# ProDocument_Schematic1_2023-08-22.net
KiCad netlist of a schematic drawn in EasyEDA Pro
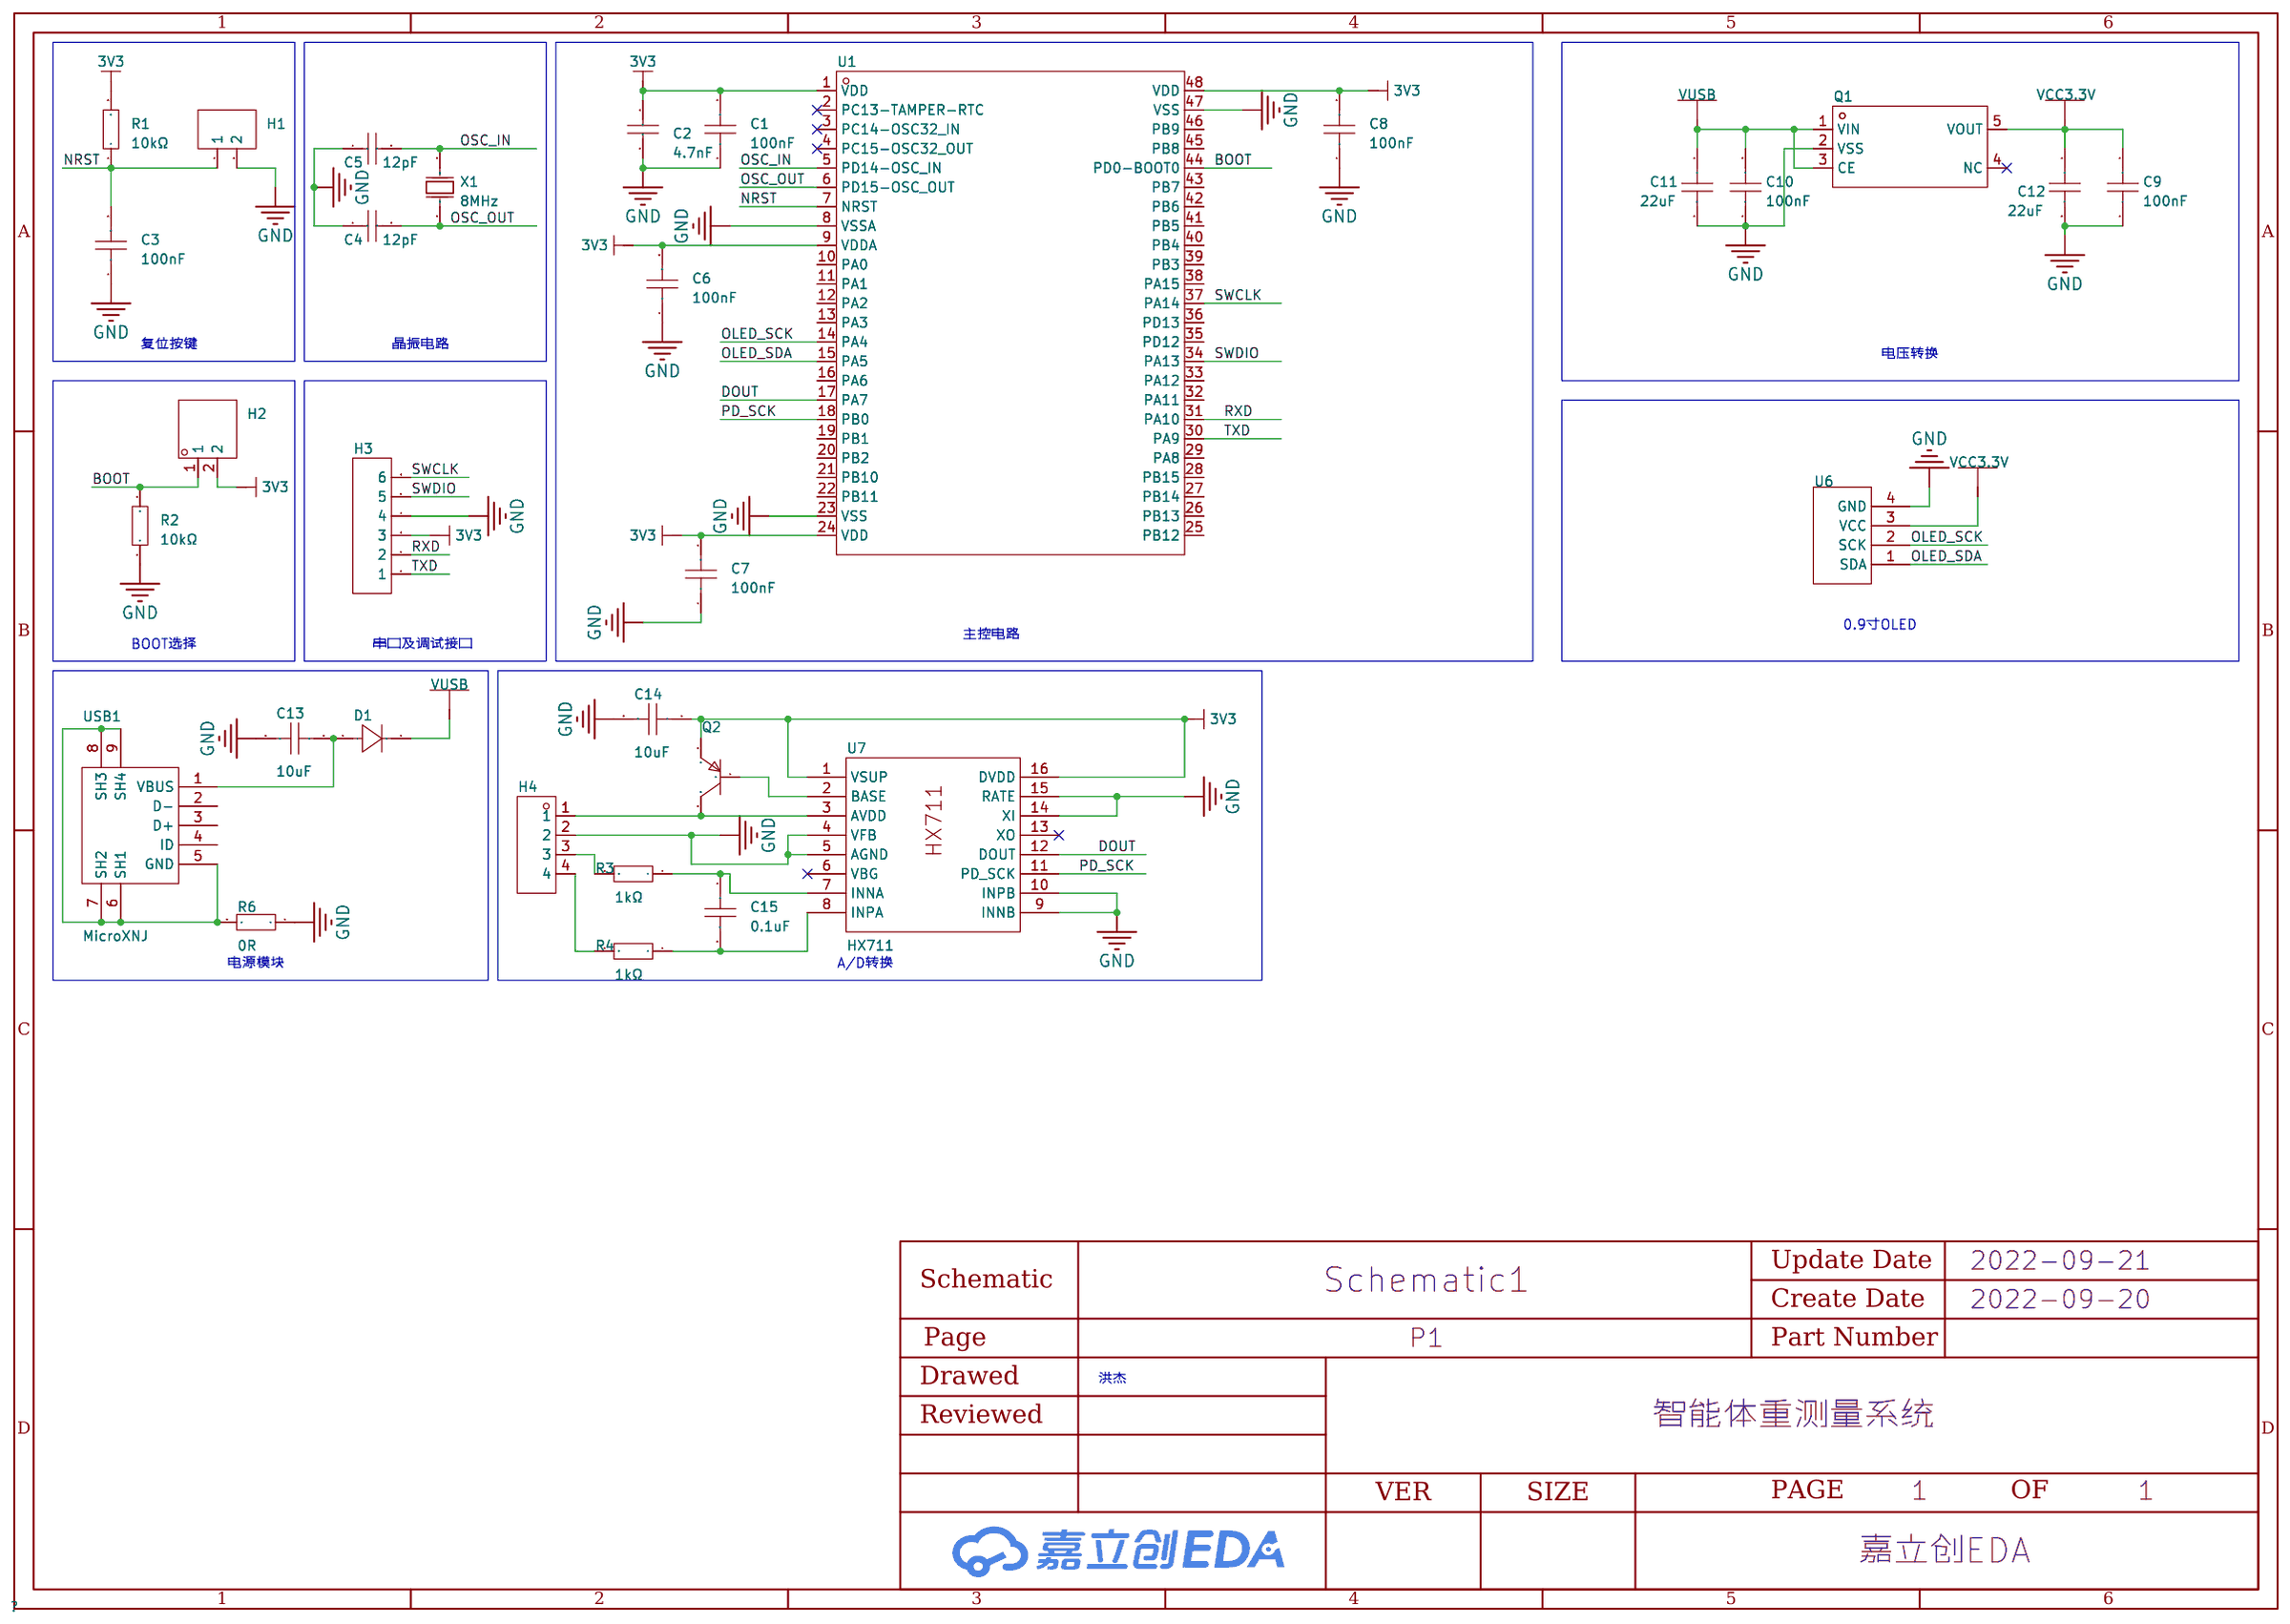
[diagram p0: schematic sheet]

(export (version "E")
  (design (tool "Eeschema 10.0.6"))
  (components
    (comp (ref "C1")
      (value "100nF")
      (footprint "easyedapro:C0603")
      (description "容值:100nF;精度:±10%;额定电压:50V;材质(温度系数):X7R;")
      (fields
        (field (name "Manufacturer Part") "CC0603KRX7R9BB104")
        (field (name "Manufacturer") "YAGEO(国巨)")
      )
      (libsource (lib "easyedapro") (part "CC0603KRX7R9BB104"))
    )
    (comp (ref "C2")
      (value "4.7nF")
      (footprint "easyedapro:C1206")
      (description "容值:4.7nF;精度:±10%;额定电压:1kV;材质(温度系数):X7R;")
      (fields (field (name "Manufacturer Part") "1206B472K102NT") (field (name "Manufacturer") "FH(风华)"))
      (libsource (lib "easyedapro") (part "1206B472K102NT"))
    )
    (comp (ref "C3")
      (value "100nF")
      (footprint "easyedapro:C0603")
      (description "容值:100nF;精度:±10%;额定电压:50V;材质(温度系数):X7R;")
      (fields
        (field (name "Manufacturer Part") "CC0603KRX7R9BB104")
        (field (name "Manufacturer") "YAGEO(国巨)")
      )
      (libsource (lib "easyedapro") (part "CC0603KRX7R9BB104"))
    )
    (comp (ref "C4")
      (value "12pF")
      (footprint "easyedapro:C0603")
      (description "温度系数:C0G;容值:12pF;精度:±5%;额定电压:50V;")
      (fields
        (field (name "Manufacturer Part") "CL10C120JB8NNNC")
        (field (name "Manufacturer") "SAMSUNG(三星)")
      )
      (libsource (lib "easyedapro") (part "CL10C120JB8NNNC"))
    )
    (comp (ref "C5")
      (value "12pF")
      (footprint "easyedapro:C0603")
      (description "温度系数:C0G;容值:12pF;精度:±5%;额定电压:50V;")
      (fields
        (field (name "Manufacturer Part") "CL10C120JB8NNNC")
        (field (name "Manufacturer") "SAMSUNG(三星)")
      )
      (libsource (lib "easyedapro") (part "CL10C120JB8NNNC"))
    )
    (comp (ref "C6")
      (value "100nF")
      (footprint "easyedapro:C0603")
      (description "容值:100nF;精度:±10%;额定电压:50V;材质(温度系数):X7R;")
      (fields
        (field (name "Manufacturer Part") "CC0603KRX7R9BB104")
        (field (name "Manufacturer") "YAGEO(国巨)")
      )
      (libsource (lib "easyedapro") (part "CC0603KRX7R9BB104"))
    )
    (comp (ref "C7")
      (value "100nF")
      (footprint "easyedapro:C0603")
      (description "容值:100nF;精度:±10%;额定电压:50V;材质(温度系数):X7R;")
      (fields
        (field (name "Manufacturer Part") "CC0603KRX7R9BB104")
        (field (name "Manufacturer") "YAGEO(国巨)")
      )
      (libsource (lib "easyedapro") (part "CC0603KRX7R9BB104"))
    )
    (comp (ref "C8")
      (value "100nF")
      (footprint "easyedapro:C0603")
      (description "容值:100nF;精度:±10%;额定电压:50V;材质(温度系数):X7R;")
      (fields
        (field (name "Manufacturer Part") "CC0603KRX7R9BB104")
        (field (name "Manufacturer") "YAGEO(国巨)")
      )
      (libsource (lib "easyedapro") (part "CC0603KRX7R9BB104"))
    )
    (comp (ref "C9")
      (value "100nF")
      (footprint "easyedapro:C0603")
      (description "容值:100nF;精度:±10%;额定电压:100V;温度系数:X7R;")
      (fields
        (field (name "Manufacturer Part") "HMK107B7104KA-T")
        (field (name "Manufacturer") "TAIYO YUDEN(太诱)")
      )
      (libsource (lib "easyedapro") (part "HMK107B7104KA-T"))
    )
    (comp (ref "C10")
      (value "100nF")
      (footprint "easyedapro:C0603")
      (description "容值:100nF;精度:±10%;额定电压:100V;温度系数:X7R;")
      (fields
        (field (name "Manufacturer Part") "HMK107B7104KA-T")
        (field (name "Manufacturer") "TAIYO YUDEN(太诱)")
      )
      (libsource (lib "easyedapro") (part "HMK107B7104KA-T"))
    )
    (comp (ref "C11")
      (value "22uF")
      (footprint "easyedapro:C0603")
      (description "容值:22uF;精度:±20%;额定电压:6.3V;温度系数:X5R;")
      (fields
        (field (name "Manufacturer Part") "GRM186R60J226ME15D")
        (field (name "Manufacturer") "muRata(村田)")
      )
      (libsource (lib "easyedapro") (part "GRM186R60J226ME15D"))
    )
    (comp (ref "C12")
      (value "22uF")
      (footprint "easyedapro:C0603")
      (description "容值:22uF;精度:±20%;额定电压:6.3V;温度系数:X5R;")
      (fields
        (field (name "Manufacturer Part") "GRM186R60J226ME15D")
        (field (name "Manufacturer") "muRata(村田)")
      )
      (libsource (lib "easyedapro") (part "GRM186R60J226ME15D"))
    )
    (comp (ref "C13")
      (value "10uF")
      (footprint "easyedapro:C0603")
      (description "容值:100nF;精度:±10%;额定电压:50V;材质(温度系数):X7R;")
      (fields
        (field (name "Manufacturer Part") "CC0603KRX7R9BB104")
        (field (name "Manufacturer") "YAGEO(国巨)")
      )
      (libsource (lib "easyedapro") (part "CC0603KRX7R9BB104"))
    )
    (comp (ref "C14")
      (value "10uF")
      (footprint "easyedapro:C0603")
      (description "容值:100nF;精度:±10%;额定电压:50V;材质(温度系数):X7R;")
      (fields
        (field (name "Manufacturer Part") "CC0603KRX7R9BB104")
        (field (name "Manufacturer") "YAGEO(国巨)")
      )
      (libsource (lib "easyedapro") (part "CC0603KRX7R9BB104"))
    )
    (comp (ref "C15")
      (value "0.1uF")
      (footprint "easyedapro:C0603")
      (description "容值:100nF;精度:±10%;额定电压:50V;材质(温度系数):X7R;")
      (fields
        (field (name "Manufacturer Part") "CC0603KRX7R9BB104")
        (field (name "Manufacturer") "YAGEO(国巨)")
      )
      (libsource (lib "easyedapro") (part "CC0603KRX7R9BB104"))
    )
    (comp (ref "D1")
      (value "~")
      (footprint "easyedapro:DO-41_BD2.4-L4.7-P8.70-D0.9-RD")
      (description "二极管配置:-;直流反向耐压(Vr):1kV;平均整流电流(Io):1A;正向压降(Vf):1.1V@1A;反向电流(Ir):5A@1kV;")
      (libsource (lib "easyedapro") (part "D_1N4007"))
    )
    (comp (ref "H1")
      (value "~")
      (footprint "easyedapro:HDR-TH_2P-P2.54-V-F")
      (libsource (lib "easyedapro") (part "Header-Female-2.54_1x2"))
    )
    (comp (ref "H2")
      (value "~")
      (footprint "easyedapro:HDR-TH_2P-P2.54-V-M-1")
      (libsource (lib "easyedapro") (part "210S-1*2P L=11.6MMGold-plated black"))
    )
    (comp (ref "H3")
      (value "~")
      (footprint "easyedapro:HDR-TH_6P-P2.54-V-M-1")
      (libsource (lib "easyedapro") (part "Header-Male-2.54_1x6"))
    )
    (comp (ref "H4")
      (value "~")
      (footprint "easyedapro:HDR-TH_4P-P2.54-V-M")
      (libsource (lib "easyedapro") (part "PZ254V-11-04P"))
    )
    (comp (ref "Q1")
      (value "~")
      (footprint "easyedapro:SOT-25-5_L3.0-W1.8-P0.95-LS3.0-BR")
      (description "输出类型:固定;输出极性:正;输出通道数:1;最大输入电压:6V;输出电压:3.3V;压差:655mV@(1A);输出电流:1A;电源纹波抑制比(PRSS):50dB@(1kHz);")
      (fields (field (name "Manufacturer Part") "XC6220B331MR-G") (field (name "Manufacturer") "TOREX(特瑞仕)"))
      (libsource (lib "easyedapro") (part "XC6220B331MR-G"))
    )
    (comp (ref "Q2")
      (value "~")
      (footprint "easyedapro:TO-236-3_L2.9-W1.3-P1.90-LS2.4-BR")
      (libsource (lib "easyedapro") (part "PNP"))
    )
    (comp (ref "R1")
      (value "10kΩ")
      (footprint "easyedapro:R0603")
      (description "电阻类型:厚膜电阻;阻值:10kΩ;精度:±1%;功率:100mW;温度系数:±100ppm/;最大工作电压:75V;工作温度范围:-55~+155;")
      (fields
        (field (name "Manufacturer Part") "0603WAF1002T5E")
        (field (name "Manufacturer") "UNI-ROYAL(厚声)")
      )
      (libsource (lib "easyedapro") (part "0603WAF1002T5E"))
    )
    (comp (ref "R2")
      (value "10kΩ")
      (footprint "easyedapro:R0603")
      (description "电阻类型:厚膜电阻;阻值:10kΩ;精度:±1%;功率:100mW;温度系数:±100ppm/;最大工作电压:75V;工作温度范围:-55~+155;")
      (fields
        (field (name "Manufacturer Part") "0603WAF1002T5E")
        (field (name "Manufacturer") "UNI-ROYAL(厚声)")
      )
      (libsource (lib "easyedapro") (part "0603WAF1002T5E"))
    )
    (comp (ref "R3")
      (value "1kΩ")
      (footprint "easyedapro:R0603")
      (description "电阻类型:厚膜电阻;阻值:10kΩ;精度:±1%;功率:100mW;温度系数:±100ppm/;最大工作电压:75V;工作温度范围:-55~+155;")
      (fields
        (field (name "Manufacturer Part") "0603WAF1002T5E")
        (field (name "Manufacturer") "UNI-ROYAL(厚声)")
      )
      (libsource (lib "easyedapro") (part "0603WAF1002T5E"))
    )
    (comp (ref "R4")
      (value "1kΩ")
      (footprint "easyedapro:R0603")
      (description "电阻类型:厚膜电阻;阻值:10kΩ;精度:±1%;功率:100mW;温度系数:±100ppm/;最大工作电压:75V;工作温度范围:-55~+155;")
      (fields
        (field (name "Manufacturer Part") "0603WAF1002T5E")
        (field (name "Manufacturer") "UNI-ROYAL(厚声)")
      )
      (libsource (lib "easyedapro") (part "0603WAF1002T5E"))
    )
    (comp (ref "R6") (value "0R") (footprint "easyedapro:R0603") (libsource (lib "easyedapro") (part "电阻")))
    (comp (ref "U1")
      (value "N32G430C8L7")
      (footprint "easyedapro:LQFP-48_L7.0-W7.0-P0.50-LS9.0-BL")
      (fields (field (name "Manufacturer") "Nations(国民技术)"))
      (libsource (lib "easyedapro") (part "N32G430C8L7"))
    )
    (comp (ref "U6")
      (value "0.91OLED-IIC-IO4")
      (footprint "easyedapro:0.91-OLED-IIC-12832")
      (libsource (lib "easyedapro") (part "0.91OLED-IIC-IO4"))
    )
    (comp (ref "U7")
      (value "HX711")
      (footprint "easyedapro:SOP-16_L10.0-W3.9-P1.27-LS6.0-BL")
      (description "A/D 位数:24;采样率（sps）:10,80;输入数:2;输入类型:Differential;")
      (fields (field (name "Manufacturer") "AVIA(海芯科技)"))
      (libsource (lib "easyedapro") (part "HX711"))
    )
    (comp (ref "USB1")
      (value "MicroXNJ")
      (footprint "easyedapro:MICRO-USB-SMD_MICROXNJ")
      (description "连接器类型:Micro-B;标准:USB 2.0;公母:母座;触点数量:5;端口数量:1;安装方式:卧贴;额定电流 - 电源:1A;工作温度范围:-20~+85;")
      (fields (field (name "Manufacturer") "SHOU HAN(首韩)"))
      (libsource (lib "easyedapro") (part "MICROXNJ"))
    )
    (comp (ref "X1")
      (value "8MHz")
      (footprint "easyedapro:OSC-SMD_L5.0-W3.2")
      (description "晶振类型:SMD 谐振器;频率:8MHz;频率公差:±30ppm;频率稳定度:±20ppm;负载电容:20pF;等效串联电阻(ESR):80Ω;工作温度:-40~85;")
      (fields (field (name "Manufacturer Part") "TAXM8M2QLFCDT1T") (field (name "Manufacturer") "TAE(雅晶鑫)"))
      (libsource (lib "easyedapro") (part "SMD-5032_2P 8M 20pf 30ppm"))
    )
  )
  (nets
    (net (code "1") (name "/BOOT") (class "Default")
      (node (ref "H2") (pin "1") (pinfunction "1_1") (pintype "input"))
      (node (ref "R2") (pin "2") (pinfunction "2_2") (pintype "input"))
      (node (ref "U1") (pin "44") (pinfunction "PD0-BOOT0_44") (pintype "input"))
    )
    (net (code "2") (name "/DOUT") (class "Default")
      (node (ref "U1") (pin "17") (pinfunction "PA7_17") (pintype "input"))
      (node (ref "U7") (pin "12") (pinfunction "DOUT_12") (pintype "input"))
    )
    (net (code "3") (name "/NRST") (class "Default")
      (node (ref "C3") (pin "2") (pinfunction "2_2") (pintype "input"))
      (node (ref "H1") (pin "1") (pinfunction "1_1") (pintype "input"))
      (node (ref "R1") (pin "1") (pinfunction "1_1") (pintype "input"))
      (node (ref "U1") (pin "7") (pinfunction "NRST_7") (pintype "input"))
    )
    (net (code "4") (name "/OLED_SCK") (class "Default")
      (node (ref "U1") (pin "14") (pinfunction "PA4_14") (pintype "input"))
      (node (ref "U6") (pin "2") (pinfunction "SCK_2") (pintype "unspecified"))
    )
    (net (code "5") (name "/OLED_SDA") (class "Default")
      (node (ref "U1") (pin "15") (pinfunction "PA5_15") (pintype "input"))
      (node (ref "U6") (pin "1") (pinfunction "SDA_1") (pintype "unspecified"))
    )
    (net (code "6") (name "/OSC_IN") (class "Default")
      (node (ref "C5") (pin "2") (pinfunction "2_2") (pintype "input"))
      (node (ref "U1") (pin "5") (pinfunction "PD14-OSC_IN_5") (pintype "input"))
      (node (ref "X1") (pin "2") (pinfunction "OSC2_2") (pintype "input"))
    )
    (net (code "7") (name "/OSC_OUT") (class "Default")
      (node (ref "C4") (pin "2") (pinfunction "2_2") (pintype "input"))
      (node (ref "U1") (pin "6") (pinfunction "PD15-OSC_OUT_6") (pintype "input"))
      (node (ref "X1") (pin "1") (pinfunction "OSC1_1") (pintype "input"))
    )
    (net (code "8") (name "/PD_SCK") (class "Default")
      (node (ref "U1") (pin "18") (pinfunction "PB0_18") (pintype "input"))
      (node (ref "U7") (pin "11") (pinfunction "PD_SCK_11") (pintype "input"))
    )
    (net (code "9") (name "/RXD") (class "Default")
      (node (ref "H3") (pin "2") (pinfunction "2_2") (pintype "input"))
      (node (ref "U1") (pin "31") (pinfunction "PA10_31") (pintype "input"))
    )
    (net (code "10") (name "/SWCLK") (class "Default")
      (node (ref "H3") (pin "6") (pinfunction "6_6") (pintype "input"))
      (node (ref "U1") (pin "37") (pinfunction "PA14_37") (pintype "input"))
    )
    (net (code "11") (name "/SWDIO") (class "Default")
      (node (ref "H3") (pin "5") (pinfunction "5_5") (pintype "input"))
      (node (ref "U1") (pin "34") (pinfunction "PA13_34") (pintype "input"))
    )
    (net (code "12") (name "/TXD") (class "Default")
      (node (ref "H3") (pin "1") (pinfunction "1_1") (pintype "input"))
      (node (ref "U1") (pin "30") (pinfunction "PA9_30") (pintype "input"))
    )
    (net (code "13") (name "3V3") (class "Default")
      (node (ref "C1") (pin "2") (pinfunction "2_2") (pintype "input"))
      (node (ref "C14") (pin "1") (pinfunction "1_1") (pintype "input"))
      (node (ref "C2") (pin "2") (pinfunction "2_2") (pintype "input"))
      (node (ref "C6") (pin "2") (pinfunction "2_2") (pintype "input"))
      (node (ref "C7") (pin "2") (pinfunction "2_2") (pintype "input"))
      (node (ref "C8") (pin "2") (pinfunction "2_2") (pintype "input"))
      (node (ref "H2") (pin "2") (pinfunction "2_2") (pintype "input"))
      (node (ref "H3") (pin "3") (pinfunction "3_3") (pintype "input"))
      (node (ref "Q2") (pin "2") (pinfunction "E_2") (pintype "input"))
      (node (ref "R1") (pin "2") (pinfunction "2_2") (pintype "input"))
      (node (ref "U1") (pin "1") (pinfunction "VDD_1") (pintype "input"))
      (node (ref "U1") (pin "24") (pinfunction "VDD_24") (pintype "input"))
      (node (ref "U1") (pin "48") (pinfunction "VDD_48") (pintype "input"))
      (node (ref "U1") (pin "9") (pinfunction "VDDA_9") (pintype "input"))
      (node (ref "U7") (pin "1") (pinfunction "VSUP_1") (pintype "input"))
      (node (ref "U7") (pin "16") (pinfunction "DVDD_16") (pintype "input"))
    )
    (net (code "14") (name "GND") (class "Default")
      (node (ref "C1") (pin "1") (pinfunction "1_1") (pintype "input"))
      (node (ref "C10") (pin "1") (pinfunction "1_1") (pintype "input"))
      (node (ref "C11") (pin "2") (pinfunction "2_2") (pintype "input"))
      (node (ref "C12") (pin "2") (pinfunction "2_2") (pintype "input"))
      (node (ref "C13") (pin "2") (pinfunction "2_2") (pintype "input"))
      (node (ref "C14") (pin "2") (pinfunction "2_2") (pintype "input"))
      (node (ref "C2") (pin "1") (pinfunction "1_1") (pintype "input"))
      (node (ref "C3") (pin "1") (pinfunction "1_1") (pintype "input"))
      (node (ref "C4") (pin "1") (pinfunction "1_1") (pintype "input"))
      (node (ref "C5") (pin "1") (pinfunction "1_1") (pintype "input"))
      (node (ref "C6") (pin "1") (pinfunction "1_1") (pintype "input"))
      (node (ref "C7") (pin "1") (pinfunction "1_1") (pintype "input"))
      (node (ref "C8") (pin "1") (pinfunction "1_1") (pintype "input"))
      (node (ref "C9") (pin "1") (pinfunction "1_1") (pintype "input"))
      (node (ref "H1") (pin "2") (pinfunction "2_2") (pintype "input"))
      (node (ref "H3") (pin "4") (pinfunction "4_4") (pintype "input"))
      (node (ref "H4") (pin "2") (pinfunction "2_2") (pintype "input"))
      (node (ref "Q1") (pin "2") (pinfunction "VSS_2") (pintype "input"))
      (node (ref "R2") (pin "1") (pinfunction "1_1") (pintype "input"))
      (node (ref "R6") (pin "1") (pinfunction "1_1") (pintype "input"))
      (node (ref "U1") (pin "23") (pinfunction "VSS_23") (pintype "input"))
      (node (ref "U1") (pin "47") (pinfunction "VSS_47") (pintype "input"))
      (node (ref "U1") (pin "8") (pinfunction "VSSA_8") (pintype "input"))
      (node (ref "U6") (pin "4") (pinfunction "GND_4") (pintype "unspecified"))
      (node (ref "U7") (pin "10") (pinfunction "INPB_10") (pintype "input"))
      (node (ref "U7") (pin "14") (pinfunction "XI_14") (pintype "input"))
      (node (ref "U7") (pin "15") (pinfunction "RATE_15") (pintype "input"))
      (node (ref "U7") (pin "4") (pinfunction "VFB_4") (pintype "input"))
      (node (ref "U7") (pin "5") (pinfunction "AGND_5") (pintype "input"))
      (node (ref "U7") (pin "9") (pinfunction "INNB_9") (pintype "input"))
    )
    (net (code "15") (name "Net-(D1-A)") (class "Default")
      (node (ref "C13") (pin "1") (pinfunction "1_1") (pintype "input"))
      (node (ref "D1") (pin "2") (pinfunction "A_2") (pintype "input"))
      (node (ref "USB1") (pin "1") (pinfunction "VBUS_1") (pintype "input"))
    )
    (net (code "16") (name "Net-(H4-Pad3)") (class "Default")
      (node (ref "H4") (pin "3") (pinfunction "3_3") (pintype "input"))
      (node (ref "R3") (pin "2") (pinfunction "2_2") (pintype "input"))
    )
    (net (code "17") (name "Net-(H4-Pad4)") (class "Default")
      (node (ref "H4") (pin "4") (pinfunction "4_4") (pintype "input"))
      (node (ref "R4") (pin "2") (pinfunction "2_2") (pintype "input"))
    )
    (net (code "18") (name "Net-(Q2-B)") (class "Default")
      (node (ref "Q2") (pin "1") (pinfunction "B_1") (pintype "input"))
      (node (ref "U7") (pin "2") (pinfunction "BASE_2") (pintype "input"))
    )
    (net (code "19") (name "Net-(Q2-C)") (class "Default")
      (node (ref "H4") (pin "1") (pinfunction "1_1") (pintype "input"))
      (node (ref "Q2") (pin "3") (pinfunction "C_3") (pintype "input"))
      (node (ref "U7") (pin "3") (pinfunction "AVDD_3") (pintype "input"))
    )
    (net (code "20") (name "Net-(U7-INNA)") (class "Default")
      (node (ref "C15") (pin "1") (pinfunction "1_1") (pintype "input"))
      (node (ref "R3") (pin "1") (pinfunction "1_1") (pintype "input"))
      (node (ref "U7") (pin "7") (pinfunction "INNA_7") (pintype "input"))
    )
    (net (code "21") (name "Net-(U7-INPA)") (class "Default")
      (node (ref "C15") (pin "2") (pinfunction "2_2") (pintype "input"))
      (node (ref "R4") (pin "1") (pinfunction "1_1") (pintype "input"))
      (node (ref "U7") (pin "8") (pinfunction "INPA_8") (pintype "input"))
    )
    (net (code "22") (name "Net-(USB1-GND)") (class "Default")
      (node (ref "R6") (pin "2") (pinfunction "2_2") (pintype "input"))
      (node (ref "USB1") (pin "5") (pinfunction "GND_5") (pintype "input"))
      (node (ref "USB1") (pin "6") (pinfunction "SH1_6") (pintype "input"))
      (node (ref "USB1") (pin "7") (pinfunction "SH2_7") (pintype "input"))
      (node (ref "USB1") (pin "8") (pinfunction "SH3_8") (pintype "input"))
      (node (ref "USB1") (pin "9") (pinfunction "SH4_9") (pintype "input"))
    )
    (net (code "23") (name "VCC3.3V") (class "Default")
      (node (ref "C12") (pin "1") (pinfunction "1_1") (pintype "input"))
      (node (ref "C9") (pin "2") (pinfunction "2_2") (pintype "input"))
      (node (ref "Q1") (pin "5") (pinfunction "VOUT_5") (pintype "input"))
      (node (ref "U6") (pin "3") (pinfunction "VCC_3") (pintype "unspecified"))
    )
    (net (code "24") (name "VUSB") (class "Default")
      (node (ref "C10") (pin "2") (pinfunction "2_2") (pintype "input"))
      (node (ref "C11") (pin "1") (pinfunction "1_1") (pintype "input"))
      (node (ref "D1") (pin "1") (pinfunction "K_1") (pintype "input"))
      (node (ref "Q1") (pin "1") (pinfunction "VIN_1") (pintype "input"))
      (node (ref "Q1") (pin "3") (pinfunction "CE_3") (pintype "input"))
    )
    (net (code "25") (name "unconnected-(Q1-NC-Pad4)") (class "Default")
      (node (ref "Q1") (pin "4") (pinfunction "NC_4") (pintype "input+no_connect"))
    )
    (net (code "26") (name "unconnected-(U1-PA0-Pad10)") (class "Default")
      (node (ref "U1") (pin "10") (pinfunction "PA0_10") (pintype "input"))
    )
    (net (code "27") (name "unconnected-(U1-PA1-Pad11)") (class "Default")
      (node (ref "U1") (pin "11") (pinfunction "PA1_11") (pintype "input"))
    )
    (net (code "28") (name "unconnected-(U1-PA2-Pad12)") (class "Default")
      (node (ref "U1") (pin "12") (pinfunction "PA2_12") (pintype "input"))
    )
    (net (code "29") (name "unconnected-(U1-PA3-Pad13)") (class "Default")
      (node (ref "U1") (pin "13") (pinfunction "PA3_13") (pintype "input"))
    )
    (net (code "30") (name "unconnected-(U1-PA6-Pad16)") (class "Default")
      (node (ref "U1") (pin "16") (pinfunction "PA6_16") (pintype "input"))
    )
    (net (code "31") (name "unconnected-(U1-PA8-Pad29)") (class "Default")
      (node (ref "U1") (pin "29") (pinfunction "PA8_29") (pintype "input"))
    )
    (net (code "32") (name "unconnected-(U1-PA11-Pad32)") (class "Default")
      (node (ref "U1") (pin "32") (pinfunction "PA11_32") (pintype "input"))
    )
    (net (code "33") (name "unconnected-(U1-PA12-Pad33)") (class "Default")
      (node (ref "U1") (pin "33") (pinfunction "PA12_33") (pintype "input"))
    )
    (net (code "34") (name "unconnected-(U1-PA15-Pad38)") (class "Default")
      (node (ref "U1") (pin "38") (pinfunction "PA15_38") (pintype "input"))
    )
    (net (code "35") (name "unconnected-(U1-PB1-Pad19)") (class "Default")
      (node (ref "U1") (pin "19") (pinfunction "PB1_19") (pintype "input"))
    )
    (net (code "36") (name "unconnected-(U1-PB2-Pad20)") (class "Default")
      (node (ref "U1") (pin "20") (pinfunction "PB2_20") (pintype "input"))
    )
    (net (code "37") (name "unconnected-(U1-PB3-Pad39)") (class "Default")
      (node (ref "U1") (pin "39") (pinfunction "PB3_39") (pintype "input"))
    )
    (net (code "38") (name "unconnected-(U1-PB4-Pad40)") (class "Default")
      (node (ref "U1") (pin "40") (pinfunction "PB4_40") (pintype "input"))
    )
    (net (code "39") (name "unconnected-(U1-PB5-Pad41)") (class "Default")
      (node (ref "U1") (pin "41") (pinfunction "PB5_41") (pintype "input"))
    )
    (net (code "40") (name "unconnected-(U1-PB6-Pad42)") (class "Default")
      (node (ref "U1") (pin "42") (pinfunction "PB6_42") (pintype "input"))
    )
    (net (code "41") (name "unconnected-(U1-PB7-Pad43)") (class "Default")
      (node (ref "U1") (pin "43") (pinfunction "PB7_43") (pintype "input"))
    )
    (net (code "42") (name "unconnected-(U1-PB8-Pad45)") (class "Default")
      (node (ref "U1") (pin "45") (pinfunction "PB8_45") (pintype "input"))
    )
    (net (code "43") (name "unconnected-(U1-PB9-Pad46)") (class "Default")
      (node (ref "U1") (pin "46") (pinfunction "PB9_46") (pintype "input"))
    )
    (net (code "44") (name "unconnected-(U1-PB10-Pad21)") (class "Default")
      (node (ref "U1") (pin "21") (pinfunction "PB10_21") (pintype "input"))
    )
    (net (code "45") (name "unconnected-(U1-PB11-Pad22)") (class "Default")
      (node (ref "U1") (pin "22") (pinfunction "PB11_22") (pintype "input"))
    )
    (net (code "46") (name "unconnected-(U1-PB12-Pad25)") (class "Default")
      (node (ref "U1") (pin "25") (pinfunction "PB12_25") (pintype "input"))
    )
    (net (code "47") (name "unconnected-(U1-PB13-Pad26)") (class "Default")
      (node (ref "U1") (pin "26") (pinfunction "PB13_26") (pintype "input"))
    )
    (net (code "48") (name "unconnected-(U1-PB14-Pad27)") (class "Default")
      (node (ref "U1") (pin "27") (pinfunction "PB14_27") (pintype "input"))
    )
    (net (code "49") (name "unconnected-(U1-PB15-Pad28)") (class "Default")
      (node (ref "U1") (pin "28") (pinfunction "PB15_28") (pintype "input"))
    )
    (net (code "50") (name "unconnected-(U1-PC13-TAMPER-RTC-Pad2)") (class "Default")
      (node (ref "U1") (pin "2") (pinfunction "PC13-TAMPER-RTC_2") (pintype "input+no_connect"))
    )
    (net (code "51") (name "unconnected-(U1-PC14-OSC32_IN-Pad3)") (class "Default")
      (node (ref "U1") (pin "3") (pinfunction "PC14-OSC32_IN_3") (pintype "input+no_connect"))
    )
    (net (code "52") (name "unconnected-(U1-PC15-OSC32_OUT-Pad4)") (class "Default")
      (node (ref "U1") (pin "4") (pinfunction "PC15-OSC32_OUT_4") (pintype "input+no_connect"))
    )
    (net (code "53") (name "unconnected-(U1-PD12-Pad35)") (class "Default")
      (node (ref "U1") (pin "35") (pinfunction "PD12_35") (pintype "input"))
    )
    (net (code "54") (name "unconnected-(U1-PD13-Pad36)") (class "Default")
      (node (ref "U1") (pin "36") (pinfunction "PD13_36") (pintype "input"))
    )
    (net (code "55") (name "unconnected-(U7-VBG-Pad6)") (class "Default")
      (node (ref "U7") (pin "6") (pinfunction "VBG_6") (pintype "input+no_connect"))
    )
    (net (code "56") (name "unconnected-(U7-XO-Pad13)") (class "Default")
      (node (ref "U7") (pin "13") (pinfunction "XO_13") (pintype "input+no_connect"))
    )
    (net (code "57") (name "unconnected-(USB1-D+-Pad3)") (class "Default")
      (node (ref "USB1") (pin "3") (pinfunction "D+_3") (pintype "input"))
    )
    (net (code "58") (name "unconnected-(USB1-D--Pad2)") (class "Default")
      (node (ref "USB1") (pin "2") (pinfunction "D-_2") (pintype "input"))
    )
    (net (code "59") (name "unconnected-(USB1-ID-Pad4)") (class "Default")
      (node (ref "USB1") (pin "4") (pinfunction "ID_4") (pintype "input"))
    )
  )
)
